# 12V_Converter.net
KiCad netlist of a schematic drawn in Altium Designer
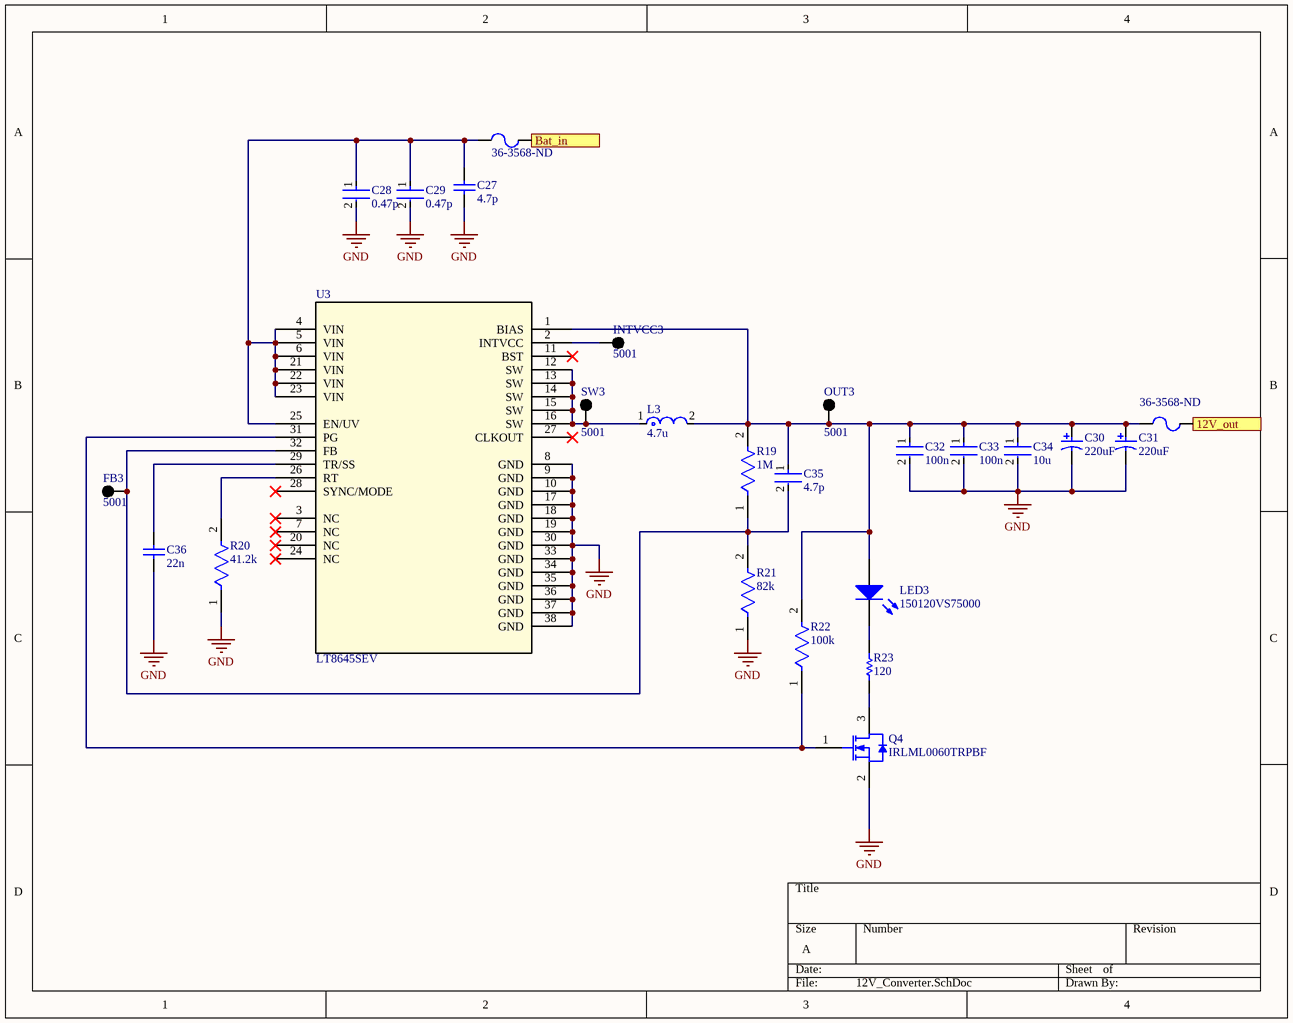
[diagram p0: 12V_Converter.SchDoc]

(export (version "E")
  (design (tool "Eeschema 10.0.6"))
  (components
    (comp (ref "C27")
      (value "4.7p")
      (footprint "CAPC1608X90X35ML10T15")
      (fields (field (name "PART NUMBER") "GRM1885C1H4R7CA01D") (field (name "MANUFACTURER") "Murata"))
      (libsource (lib "Altium Content Vault") (part "CAP"))
    )
    (comp (ref "C28")
      (value "0.47p")
      (footprint "FP-CL21-IPC_B")
      (description "CL21 Series 0805 0.47pF 50V ±0.1pF Tolerance C0G Multilayer Ceramic Chip Capacitor")
      (fields (field (name "VOLTAGE") "50V"))
      (libsource (lib "Altium Content Vault") (part "b4654b650e69147ec39a6b967a45e02"))
    )
    (comp (ref "C29")
      (value "0.47p")
      (footprint "FP-CL21-IPC_B")
      (description "CL21 Series 0805 0.47pF 50V ±0.1pF Tolerance C0G Multilayer Ceramic Chip Capacitor")
      (fields (field (name "VOLTAGE") "50V"))
      (libsource (lib "Altium Content Vault") (part "b4654b650e69147ec39a6b967a45e02"))
    )
    (comp (ref "C30")
      (value "220uF")
      (footprint "CAPPR65-500-1250X1000X1350")
      (description "Aluminum Electrolytic Capacitor, 220 uF, +/- 20%, 50 V, -40 to 85 degC, 2-Pin THD, RoHS, Bulk")
      (libsource (lib "Altium Content Vault") (part "CAP-P-2"))
    )
    (comp (ref "C31")
      (value "220uF")
      (footprint "CAPPR65-500-1250X1000X1350")
      (description "Aluminum Electrolytic Capacitor, 220 uF, +/- 20%, 50 V, -40 to 85 degC, 2-Pin THD, RoHS, Bulk")
      (libsource (lib "Altium Content Vault") (part "CAP-P-2"))
    )
    (comp (ref "C32")
      (value "100n")
      (footprint "FP-CL10-IPC_A")
      (description "Cap Ceramic 100nF 50V X7R ±10% Pad SMD 0603 +125°C T/R")
      (fields (field (name "VOLTAGE") "50V") (field (name "TOLERANCE") "10%"))
      (libsource (lib "Altium Content Vault") (part "b4654b650e69147ec39a6b967a45e02"))
    )
    (comp (ref "C33")
      (value "100n")
      (footprint "FP-CL10-IPC_A")
      (description "Cap Ceramic 100nF 50V X7R ±10% Pad SMD 0603 +125°C T/R")
      (fields (field (name "VOLTAGE") "50V") (field (name "TOLERANCE") "10%"))
      (libsource (lib "Altium Content Vault") (part "b4654b650e69147ec39a6b967a45e02"))
    )
    (comp (ref "C34")
      (value "10u")
      (footprint "FP-CGA6P-IPC_A")
      (description "Cap Ceramic 10uF 50V X7S 10% Pad SMD 1210 +125°C Automotive T/R")
      (fields (field (name "TOLERANCE") "10%") (field (name "VOLTAGE") "50V"))
      (libsource (lib "Altium Content Vault") (part "b4654b650e69147ec39a6b967a45e02"))
    )
    (comp (ref "C35")
      (value "4.7p")
      (footprint "FP-0603-L_1_6_0_15-W_0_81-MFG")
      (description "General Purpose Ceramic Capacitor, 0603, 4.7pF, 0.25pF, NP0, 30ppm/°C, 50V")
      (libsource (lib "Altium Content Vault") (part "02cd4be3c70576c341d710602a673aa"))
    )
    (comp (ref "C36")
      (value "22n")
      (footprint "CAPC1608X90X35ML10T15")
      (fields (field (name "MANUFACTURER") "Murata") (field (name "PART NUMBER") "GRM188R71H223KA01D"))
      (libsource (lib "Altium Content Vault") (part "CAP"))
    )
    (comp (ref "F5")
      (value "36-3568-ND")
      (footprint "PCBComponent_1")
      (libsource (lib "3568FuseHolder1") (part "Fuse_Holder"))
    )
    (comp (ref "F6")
      (value "36-3568-ND")
      (footprint "PCBComponent_1")
      (libsource (lib "3568FuseHolder1") (part "Fuse_Holder"))
    )
    (comp (ref "FB3")
      (value "5001")
      (footprint "KSTN-5001")
      (description "Test Point, Black, 1-Pin THD, RoHS, Bulk")
      (fields (field (name "MANUFACTURER") "Keystone"))
      (libsource (lib "Altium Content Vault") (part "KSTN-TP-5001"))
    )
    (comp (ref "INTVCC3")
      (value "5001")
      (footprint "KSTN-5001")
      (description "Test Point, Black, 1-Pin THD, RoHS, Bulk")
      (fields (field (name "MANUFACTURER") "Keystone"))
      (libsource (lib "Altium Content Vault") (part "KSTN-TP-5001"))
    )
    (comp (ref "L3")
      (value "4.7u")
      (footprint "FP-XAL6060-472MEC-MFG")
      (description "Surface Mount Power Inductor, AEC-Q200 XAL6060 Series, 4.7 H, 20%, Shielded, 0.0144 ohm, 11 A")
      (fields (field (name "TOLERANCE") "20%"))
      (libsource (lib "Altium Content Vault") (part "4cc4b267dca4c8e51f7102f422741d8"))
    )
    (comp (ref "LED3")
      (value "150120VS75000")
      (footprint "1206_A")
      (description "SMD mono-color Chip LED, WL-SMCW, Bright Green")
      (fields (field (name "MANUFACTURER") "Wuerth Elektronik"))
      (libsource (lib "Altium Content Vault") (part "WE-LED_K1A2-2"))
    )
    (comp (ref "OUT3")
      (value "5001")
      (footprint "KSTN-5001")
      (description "Test Point, Black, 1-Pin THD, RoHS, Bulk")
      (fields (field (name "MANUFACTURER") "Keystone"))
      (libsource (lib "Altium Content Vault") (part "KSTN-TP-5001"))
    )
    (comp (ref "Q4")
      (value "IRLML0060TRPBF")
      (footprint "INTR-SOT-23-3_V")
      (description "HEXFET Power MOSFET\r\n, 60 V, 2.7 A, -55 to 150 degC, 3-Pin SOT-23, RoHS, Tape and Reel")
      (fields (field (name "MANUFACTURER") "International Rectifier"))
      (libsource (lib "Altium Content Vault") (part "NEMOS-GSD-3"))
    )
    (comp (ref "R19")
      (value "1M")
      (footprint "FP-CRCW0603-e3-MFG")
      (description "RES Thick Film, 1MΩ, 1%, 0.1W, 100ppm/°C, 0603")
      (fields (field (name "TOLERANCE") "1%"))
      (libsource (lib "Altium Content Vault") (part "1029c3af85768c4190bb7ad29bc67b5"))
    )
    (comp (ref "R20")
      (value "41.2k")
      (footprint "FP-CRCW0603-e3-MFG")
      (description "RES Thick Film, 41.2kΩ, 1%, 0.1W, 100ppm/°C, 0603")
      (fields (field (name "TOLERANCE") "1%"))
      (libsource (lib "Altium Content Vault") (part "1029c3af85768c4190bb7ad29bc67b5"))
    )
    (comp (ref "R21")
      (value "82k")
      (footprint "FP-CRCW0603-e3-IPC_C")
      (description "RES Thick Film, 82kΩ, 1%, 0.1W, 100ppm/°C, 0603")
      (fields (field (name "TOLERANCE") "1%"))
      (libsource (lib "Altium Content Vault") (part "1029c3af85768c4190bb7ad29bc67b5"))
    )
    (comp (ref "R22")
      (value "100k")
      (footprint "FP-RC0603-0_55-MFG")
      (description "RES SMD 100K OHM 1% 1/10W 0603")
      (fields (field (name "TOLERANCE") "1%"))
      (libsource (lib "Altium Content Vault") (part "1029c3af85768c4190bb7ad29bc67b5"))
    )
    (comp (ref "R23")
      (value "120")
      (footprint "RESC1609X55X30ML15T15")
      (description "Chip Resistor, 120 Ohm, +/- 1%, 0.1 W, -55 to 155 degC, 0603 (1608 Metric), RoHS, Tape and Reel")
      (fields (field (name "TOLERANCE") "1%") (field (name "MANUFACTURER") "Panasonic"))
      (libsource (lib "Altium Content Vault") (part "RES-2"))
    )
    (comp (ref "SW3")
      (value "5001")
      (footprint "KSTN-5001")
      (description "Test Point, Black, 1-Pin THD, RoHS, Bulk")
      (fields (field (name "MANUFACTURER") "Keystone"))
      (libsource (lib "Altium Content Vault") (part "KSTN-TP-5001"))
    )
    (comp (ref "U3")
      (value "LT8645SEV")
      (footprint "LQFN-32")
      (description "No Description Available")
      (fields (field (name "COPYRIGHT") "Copyright (C) 2018 Accelerated Designs. All rights reserved"))
      (libsource (lib "LT8645S_Library") (part "LT8645SEV"))
    )
  )
  (nets
    (net (code "1") (name "/12V_out") (class "Default")
      (node (ref "F6") (pin "2") (pinfunction "2_2") (pintype "passive"))
    )
    (net (code "2") (name "/Bat_in") (class "Default")
      (node (ref "F5") (pin "2") (pinfunction "2_2") (pintype "passive"))
    )
    (net (code "3") (name "GND") (class "Default")
      (node (ref "C27") (pin "1") (pinfunction "1_1") (pintype "passive"))
      (node (ref "C28") (pin "2") (pinfunction "2_2") (pintype "passive"))
      (node (ref "C29") (pin "2") (pinfunction "2_2") (pintype "passive"))
      (node (ref "C30") (pin "2") (pinfunction "2_2") (pintype "passive"))
      (node (ref "C31") (pin "2") (pinfunction "2_2") (pintype "passive"))
      (node (ref "C32") (pin "2") (pinfunction "2_2") (pintype "passive"))
      (node (ref "C33") (pin "2") (pinfunction "2_2") (pintype "passive"))
      (node (ref "C34") (pin "2") (pinfunction "2_2") (pintype "passive"))
      (node (ref "C36") (pin "1") (pinfunction "1_1") (pintype "passive"))
      (node (ref "Q4") (pin "2") (pinfunction "S_2") (pintype "passive"))
      (node (ref "R20") (pin "1") (pinfunction "1_1") (pintype "passive"))
      (node (ref "R21") (pin "1") (pinfunction "1_1") (pintype "passive"))
      (node (ref "U3") (pin "10") (pinfunction "GND_10") (pintype "passive"))
      (node (ref "U3") (pin "17") (pinfunction "GND_17") (pintype "passive"))
      (node (ref "U3") (pin "18") (pinfunction "GND_18") (pintype "passive"))
      (node (ref "U3") (pin "19") (pinfunction "GND_19") (pintype "passive"))
      (node (ref "U3") (pin "30") (pinfunction "GND_30") (pintype "passive"))
      (node (ref "U3") (pin "33") (pinfunction "GND_33") (pintype "passive"))
      (node (ref "U3") (pin "34") (pinfunction "GND_34") (pintype "passive"))
      (node (ref "U3") (pin "35") (pinfunction "GND_35") (pintype "passive"))
      (node (ref "U3") (pin "36") (pinfunction "GND_36") (pintype "passive"))
      (node (ref "U3") (pin "37") (pinfunction "GND_37") (pintype "passive"))
      (node (ref "U3") (pin "38") (pinfunction "GND_38") (pintype "passive"))
      (node (ref "U3") (pin "8") (pinfunction "GND_8") (pintype "passive"))
      (node (ref "U3") (pin "9") (pinfunction "GND_9") (pintype "passive"))
    )
    (net (code "4") (name "Net-(L3-Pad1)") (class "Default")
      (node (ref "L3") (pin "1") (pinfunction "1_1") (pintype "passive"))
      (node (ref "SW3") (pin "1") (pintype "passive"))
      (node (ref "U3") (pin "12") (pinfunction "SW_12") (pintype "passive"))
      (node (ref "U3") (pin "13") (pinfunction "SW_13") (pintype "passive"))
      (node (ref "U3") (pin "14") (pinfunction "SW_14") (pintype "passive"))
      (node (ref "U3") (pin "15") (pinfunction "SW_15") (pintype "passive"))
      (node (ref "U3") (pin "16") (pinfunction "SW_16") (pintype "passive"))
    )
    (net (code "5") (name "Net-(LED3-A)") (class "Default")
      (node (ref "C30") (pin "1") (pinfunction "1_1") (pintype "passive"))
      (node (ref "C31") (pin "1") (pinfunction "1_1") (pintype "passive"))
      (node (ref "C32") (pin "1") (pinfunction "1_1") (pintype "passive"))
      (node (ref "C33") (pin "1") (pinfunction "1_1") (pintype "passive"))
      (node (ref "C34") (pin "1") (pinfunction "1_1") (pintype "passive"))
      (node (ref "C35") (pin "1") (pinfunction "1_1") (pintype "passive"))
      (node (ref "F6") (pin "1") (pinfunction "1_1") (pintype "passive"))
      (node (ref "L3") (pin "2") (pinfunction "2_2") (pintype "passive"))
      (node (ref "LED3") (pin "2") (pinfunction "A_2") (pintype "passive"))
      (node (ref "OUT3") (pin "1") (pintype "passive"))
      (node (ref "R19") (pin "2") (pinfunction "2_2") (pintype "passive"))
      (node (ref "R22") (pin "2") (pinfunction "2_2") (pintype "passive"))
      (node (ref "U3") (pin "1") (pinfunction "BIAS_1") (pintype "passive"))
    )
    (net (code "6") (name "Net-(LED3-K)") (class "Default")
      (node (ref "LED3") (pin "1") (pinfunction "K_1") (pintype "passive"))
      (node (ref "R23") (pin "2") (pinfunction "2_2") (pintype "passive"))
    )
    (net (code "7") (name "Net-(Q4-D)") (class "Default")
      (node (ref "Q4") (pin "3") (pinfunction "D_3") (pintype "passive"))
      (node (ref "R23") (pin "1") (pinfunction "1_1") (pintype "passive"))
    )
    (net (code "8") (name "Net-(Q4-G)") (class "Default")
      (node (ref "Q4") (pin "1") (pinfunction "G_1") (pintype "passive"))
      (node (ref "R22") (pin "1") (pinfunction "1_1") (pintype "passive"))
      (node (ref "U3") (pin "31") (pinfunction "PG_31") (pintype "passive"))
    )
    (net (code "9") (name "Net-(U3-EN{slash}UV)") (class "Default")
      (node (ref "C27") (pin "2") (pinfunction "2_2") (pintype "passive"))
      (node (ref "C28") (pin "1") (pinfunction "1_1") (pintype "passive"))
      (node (ref "C29") (pin "1") (pinfunction "1_1") (pintype "passive"))
      (node (ref "F5") (pin "1") (pinfunction "1_1") (pintype "passive"))
      (node (ref "U3") (pin "21") (pinfunction "VIN_21") (pintype "passive"))
      (node (ref "U3") (pin "22") (pinfunction "VIN_22") (pintype "passive"))
      (node (ref "U3") (pin "23") (pinfunction "VIN_23") (pintype "passive"))
      (node (ref "U3") (pin "25") (pinfunction "EN/UV_25") (pintype "passive"))
      (node (ref "U3") (pin "4") (pinfunction "VIN_4") (pintype "passive"))
      (node (ref "U3") (pin "5") (pinfunction "VIN_5") (pintype "passive"))
      (node (ref "U3") (pin "6") (pinfunction "VIN_6") (pintype "passive"))
    )
    (net (code "10") (name "Net-(U3-FB)") (class "Default")
      (node (ref "C35") (pin "2") (pinfunction "2_2") (pintype "passive"))
      (node (ref "FB3") (pin "1") (pintype "passive"))
      (node (ref "R19") (pin "1") (pinfunction "1_1") (pintype "passive"))
      (node (ref "R21") (pin "2") (pinfunction "2_2") (pintype "passive"))
      (node (ref "U3") (pin "32") (pinfunction "FB_32") (pintype "passive"))
    )
    (net (code "11") (name "Net-(U3-INTVCC)") (class "Default")
      (node (ref "INTVCC3") (pin "1") (pintype "passive"))
      (node (ref "U3") (pin "2") (pinfunction "INTVCC_2") (pintype "passive"))
    )
    (net (code "12") (name "Net-(U3-RT)") (class "Default")
      (node (ref "R20") (pin "2") (pinfunction "2_2") (pintype "passive"))
      (node (ref "U3") (pin "26") (pinfunction "RT_26") (pintype "passive"))
    )
    (net (code "13") (name "Net-(U3-TR{slash}SS)") (class "Default")
      (node (ref "C36") (pin "2") (pinfunction "2_2") (pintype "passive"))
      (node (ref "U3") (pin "29") (pinfunction "TR/SS_29") (pintype "passive"))
    )
    (net (code "14") (name "unconnected-(U3-BST-Pad11)") (class "Default")
      (node (ref "U3") (pin "11") (pinfunction "BST_11") (pintype "passive+no_connect"))
    )
    (net (code "15") (name "unconnected-(U3-CLKOUT-Pad27)") (class "Default")
      (node (ref "U3") (pin "27") (pinfunction "CLKOUT_27") (pintype "passive+no_connect"))
    )
    (net (code "16") (name "unconnected-(U3-NC-Pad3)") (class "Default")
      (node (ref "U3") (pin "3") (pinfunction "NC_3") (pintype "passive+no_connect"))
    )
    (net (code "17") (name "unconnected-(U3-NC-Pad7)") (class "Default")
      (node (ref "U3") (pin "7") (pinfunction "NC_7") (pintype "passive+no_connect"))
    )
    (net (code "18") (name "unconnected-(U3-NC-Pad20)") (class "Default")
      (node (ref "U3") (pin "20") (pinfunction "NC_20") (pintype "passive+no_connect"))
    )
    (net (code "19") (name "unconnected-(U3-NC-Pad24)") (class "Default")
      (node (ref "U3") (pin "24") (pinfunction "NC_24") (pintype "passive+no_connect"))
    )
    (net (code "20") (name "unconnected-(U3-SYNC{slash}MODE-Pad28)") (class "Default")
      (node (ref "U3") (pin "28") (pinfunction "SYNC/MODE_28") (pintype "passive+no_connect"))
    )
  )
)
